# as14120_fpga_ddr.net
KiCad netlist of a schematic drawn in Altium Designer
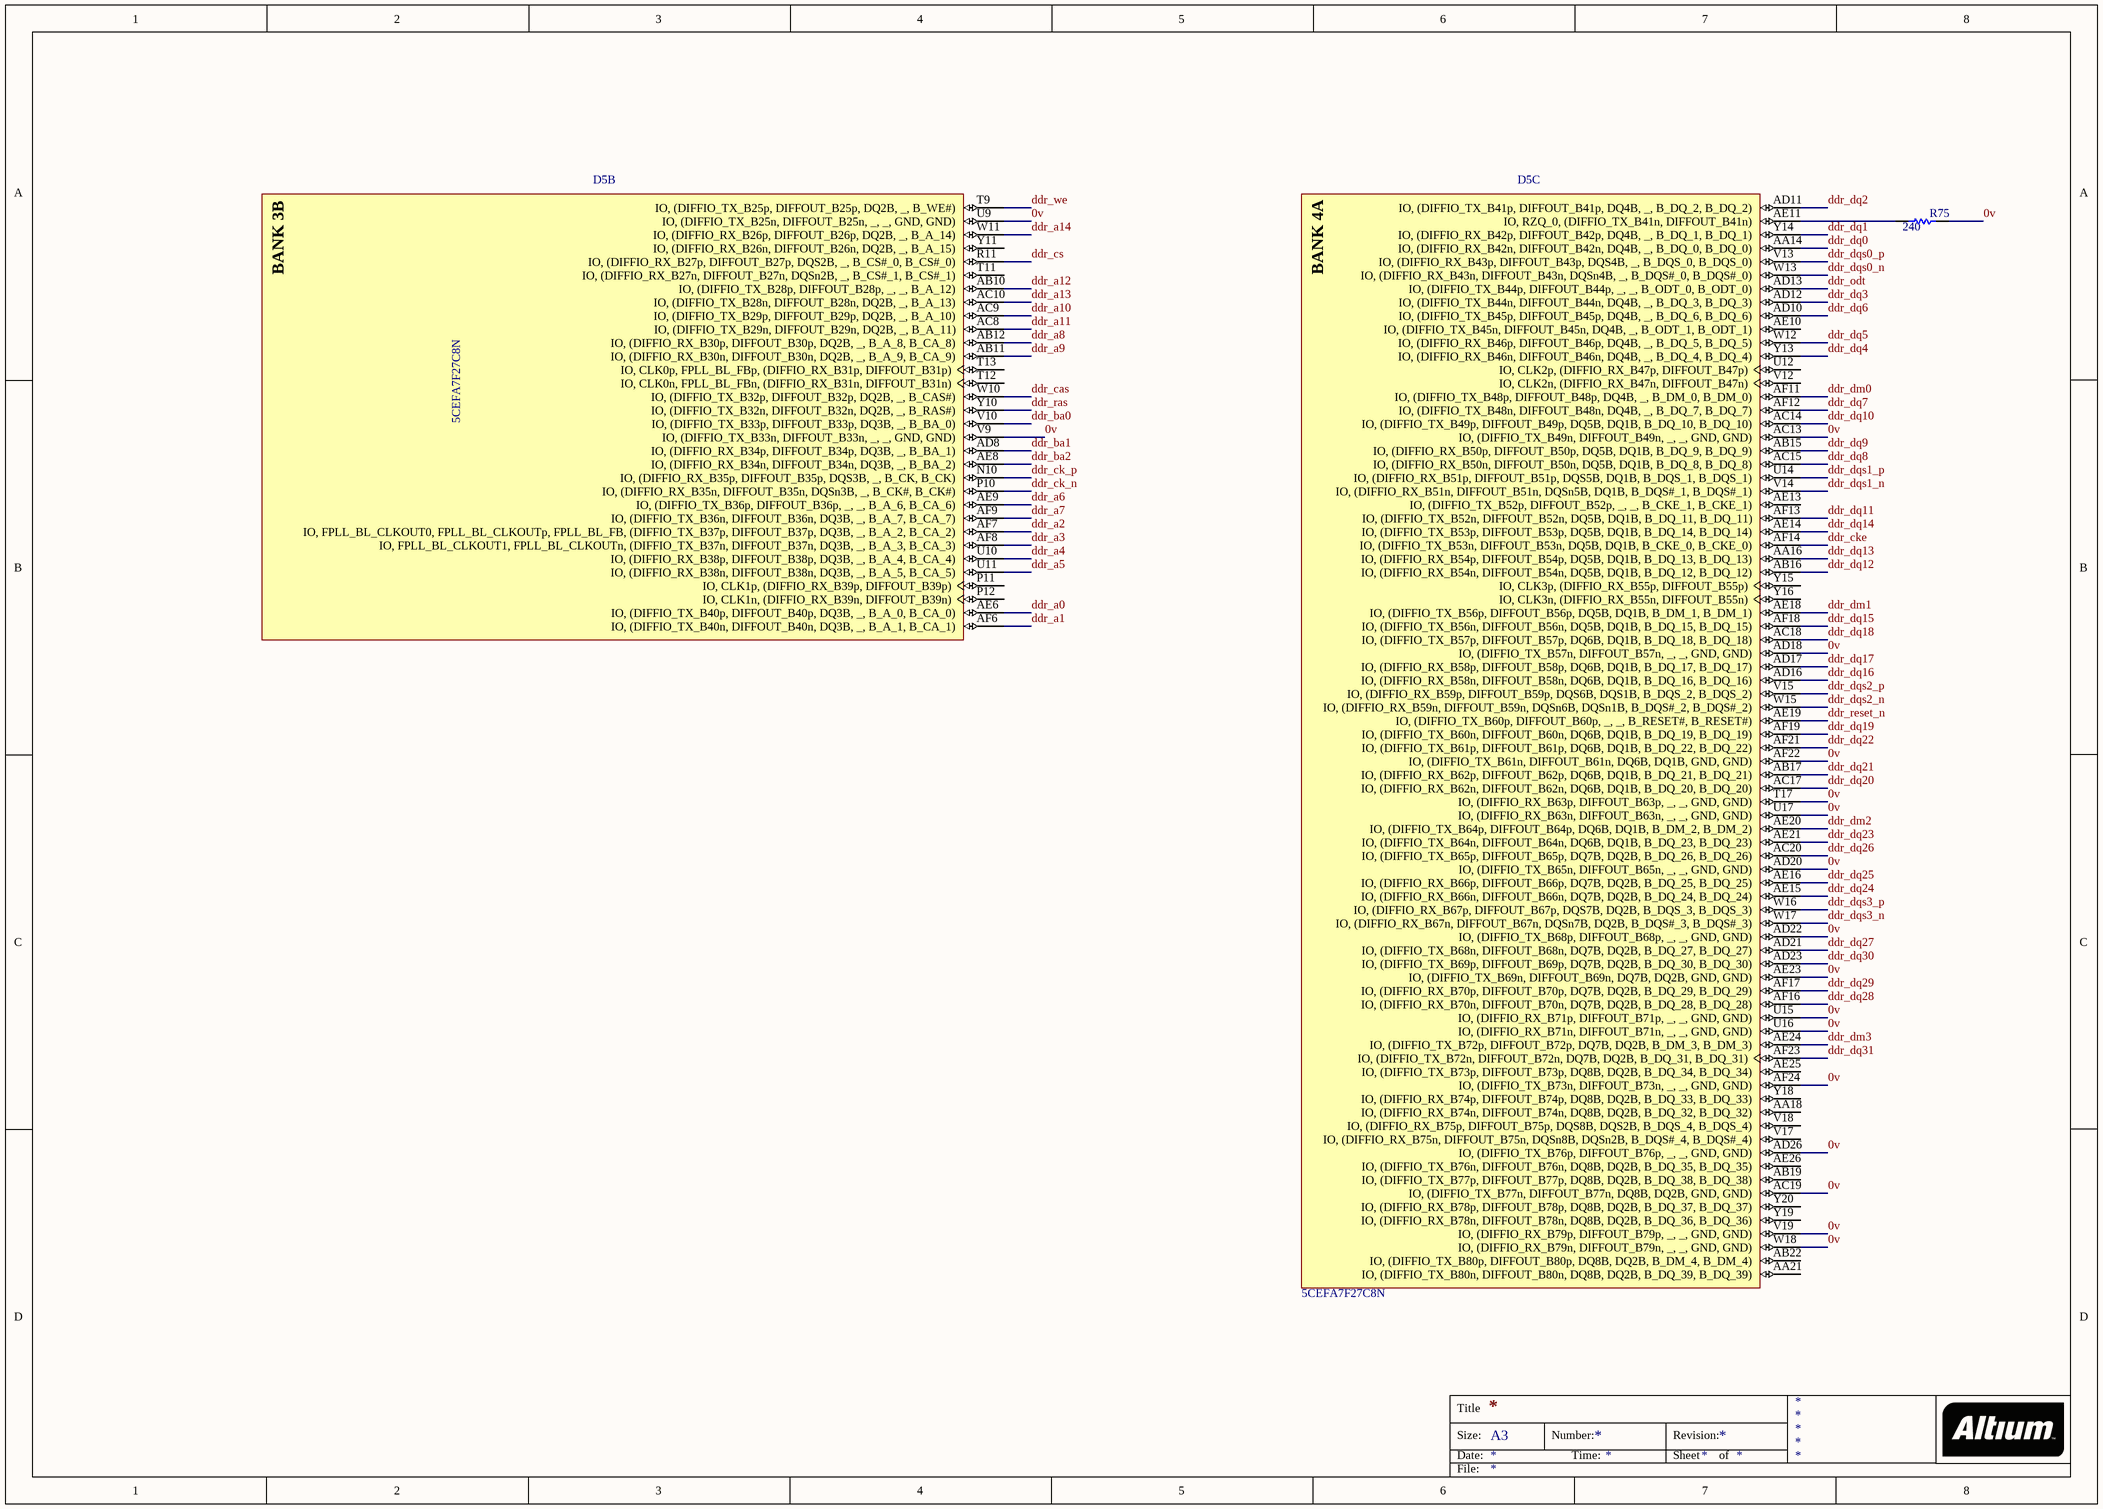
[diagram p0: as14120_fpga_ddr.SchDoc]

(export (version "E")
  (design (tool "Eeschema 10.0.6"))
  (components
    (comp (ref "D5")
      (value "5CEFA7F27C8N")
      (footprint "ALTR-672-FBGA-2000A")
      (fields (field (name "MANUFACTURER") "Altera"))
      (libsource (lib "Altera Cyclone V E") (part "5CEFA7F27C8N"))
    )
    (comp (ref "R75")
      (value "240")
      (footprint "RESC0805(2012)_L")
      (description "1K 0.125W 1% 0805 (2012 Metric)  SMD")
      (fields (field (name "TOLERANCE") "1 %") (field (name "POWER") "0.125 W"))
      (libsource (lib "as14120") (part "RES_0805"))
    )
  )
  (nets
    (net (code "1") (name "/0v") (class "Default")
      (node (ref "D5") (pin "AC13") (pinfunction "IO,_(DIFFIO_TX_B49n,_DIFFOUT_B49n,__,__,_GND,_GND)_AC13") (pintype "bidirectional"))
      (node (ref "D5") (pin "AC19") (pinfunction "IO,_(DIFFIO_TX_B77n,_DIFFOUT_B77n,_DQ8B,_DQ2B,_GND,_GND)_AC19") (pintype "bidirectional"))
      (node (ref "D5") (pin "AD18") (pinfunction "IO,_(DIFFIO_TX_B57n,_DIFFOUT_B57n,__,__,_GND,_GND)_AD18") (pintype "bidirectional"))
      (node (ref "D5") (pin "AD20") (pinfunction "IO,_(DIFFIO_TX_B65n,_DIFFOUT_B65n,__,__,_GND,_GND)_AD20") (pintype "bidirectional"))
      (node (ref "D5") (pin "AD22") (pinfunction "IO,_(DIFFIO_TX_B68p,_DIFFOUT_B68p,__,__,_GND,_GND)_AD22") (pintype "bidirectional"))
      (node (ref "D5") (pin "AD26") (pinfunction "IO,_(DIFFIO_TX_B76p,_DIFFOUT_B76p,__,__,_GND,_GND)_AD26") (pintype "bidirectional"))
      (node (ref "D5") (pin "AE23") (pinfunction "IO,_(DIFFIO_TX_B69n,_DIFFOUT_B69n,_DQ7B,_DQ2B,_GND,_GND)_AE23") (pintype "bidirectional"))
      (node (ref "D5") (pin "AF22") (pinfunction "IO,_(DIFFIO_TX_B61n,_DIFFOUT_B61n,_DQ6B,_DQ1B,_GND,_GND)_AF22") (pintype "bidirectional"))
      (node (ref "D5") (pin "AF24") (pinfunction "IO,_(DIFFIO_TX_B73n,_DIFFOUT_B73n,__,__,_GND,_GND)_AF24") (pintype "bidirectional"))
      (node (ref "D5") (pin "T17") (pinfunction "IO,_(DIFFIO_RX_B63p,_DIFFOUT_B63p,__,__,_GND,_GND)_T17") (pintype "bidirectional"))
      (node (ref "D5") (pin "U15") (pinfunction "IO,_(DIFFIO_RX_B71p,_DIFFOUT_B71p,__,__,_GND,_GND)_U15") (pintype "bidirectional"))
      (node (ref "D5") (pin "U16") (pinfunction "IO,_(DIFFIO_RX_B71n,_DIFFOUT_B71n,__,__,_GND,_GND)_U16") (pintype "bidirectional"))
      (node (ref "D5") (pin "U17") (pinfunction "IO,_(DIFFIO_RX_B63n,_DIFFOUT_B63n,__,__,_GND,_GND)_U17") (pintype "bidirectional"))
      (node (ref "D5") (pin "U9") (pinfunction "IO,_(DIFFIO_TX_B25n,_DIFFOUT_B25n,__,__,_GND,_GND)_U9") (pintype "bidirectional"))
      (node (ref "D5") (pin "V19") (pinfunction "IO,_(DIFFIO_RX_B79p,_DIFFOUT_B79p,__,__,_GND,_GND)_V19") (pintype "bidirectional"))
      (node (ref "D5") (pin "V9") (pinfunction "IO,_(DIFFIO_TX_B33n,_DIFFOUT_B33n,__,__,_GND,_GND)_V9") (pintype "bidirectional"))
      (node (ref "D5") (pin "W18") (pinfunction "IO,_(DIFFIO_RX_B79n,_DIFFOUT_B79n,__,__,_GND,_GND)_W18") (pintype "bidirectional"))
      (node (ref "R75") (pin "2") (pinfunction "2_2") (pintype "passive"))
    )
    (net (code "2") (name "/ddr_a0") (class "Default")
      (node (ref "D5") (pin "AE6") (pinfunction "IO,_(DIFFIO_TX_B40p,_DIFFOUT_B40p,_DQ3B,__,_B_A_0,_B_CA_0)_AE6") (pintype "bidirectional"))
    )
    (net (code "3") (name "/ddr_a1") (class "Default")
      (node (ref "D5") (pin "AF6") (pinfunction "IO,_(DIFFIO_TX_B40n,_DIFFOUT_B40n,_DQ3B,__,_B_A_1,_B_CA_1)_AF6") (pintype "bidirectional"))
    )
    (net (code "4") (name "/ddr_a2") (class "Default")
      (node (ref "D5") (pin "AF7") (pinfunction "IO,_FPLL_BL_CLKOUT0,_FPLL_BL_CLKOUTp,_FPLL_BL_FB,_(DIFFIO_TX_B37p,_DIFFOUT_B37p,_DQ3B,__,_B_A_2,_B_CA_2)_AF7") (pintype "bidirectional"))
    )
    (net (code "5") (name "/ddr_a3") (class "Default")
      (node (ref "D5") (pin "AF8") (pinfunction "IO,_FPLL_BL_CLKOUT1,_FPLL_BL_CLKOUTn,_(DIFFIO_TX_B37n,_DIFFOUT_B37n,_DQ3B,__,_B_A_3,_B_CA_3)_AF8") (pintype "bidirectional"))
    )
    (net (code "6") (name "/ddr_a4") (class "Default")
      (node (ref "D5") (pin "U10") (pinfunction "IO,_(DIFFIO_RX_B38p,_DIFFOUT_B38p,_DQ3B,__,_B_A_4,_B_CA_4)_U10") (pintype "bidirectional"))
    )
    (net (code "7") (name "/ddr_a5") (class "Default")
      (node (ref "D5") (pin "U11") (pinfunction "IO,_(DIFFIO_RX_B38n,_DIFFOUT_B38n,_DQ3B,__,_B_A_5,_B_CA_5)_U11") (pintype "bidirectional"))
    )
    (net (code "8") (name "/ddr_a6") (class "Default")
      (node (ref "D5") (pin "AE9") (pinfunction "IO,_(DIFFIO_TX_B36p,_DIFFOUT_B36p,__,__,_B_A_6,_B_CA_6)_AE9") (pintype "bidirectional"))
    )
    (net (code "9") (name "/ddr_a7") (class "Default")
      (node (ref "D5") (pin "AF9") (pinfunction "IO,_(DIFFIO_TX_B36n,_DIFFOUT_B36n,_DQ3B,__,_B_A_7,_B_CA_7)_AF9") (pintype "bidirectional"))
    )
    (net (code "10") (name "/ddr_a8") (class "Default")
      (node (ref "D5") (pin "AB12") (pinfunction "IO,_(DIFFIO_RX_B30p,_DIFFOUT_B30p,_DQ2B,__,_B_A_8,_B_CA_8)_AB12") (pintype "bidirectional"))
    )
    (net (code "11") (name "/ddr_a9") (class "Default")
      (node (ref "D5") (pin "AB11") (pinfunction "IO,_(DIFFIO_RX_B30n,_DIFFOUT_B30n,_DQ2B,__,_B_A_9,_B_CA_9)_AB11") (pintype "bidirectional"))
    )
    (net (code "12") (name "/ddr_a10") (class "Default")
      (node (ref "D5") (pin "AC9") (pinfunction "IO,_(DIFFIO_TX_B29p,_DIFFOUT_B29p,_DQ2B,__,_B_A_10)_AC9") (pintype "bidirectional"))
    )
    (net (code "13") (name "/ddr_a11") (class "Default")
      (node (ref "D5") (pin "AC8") (pinfunction "IO,_(DIFFIO_TX_B29n,_DIFFOUT_B29n,_DQ2B,__,_B_A_11)_AC8") (pintype "bidirectional"))
    )
    (net (code "14") (name "/ddr_a12") (class "Default")
      (node (ref "D5") (pin "AB10") (pinfunction "IO,_(DIFFIO_TX_B28p,_DIFFOUT_B28p,__,__,_B_A_12)_AB10") (pintype "bidirectional"))
    )
    (net (code "15") (name "/ddr_a13") (class "Default")
      (node (ref "D5") (pin "AC10") (pinfunction "IO,_(DIFFIO_TX_B28n,_DIFFOUT_B28n,_DQ2B,__,_B_A_13)_AC10") (pintype "bidirectional"))
    )
    (net (code "16") (name "/ddr_a14") (class "Default")
      (node (ref "D5") (pin "W11") (pinfunction "IO,_(DIFFIO_RX_B26p,_DIFFOUT_B26p,_DQ2B,__,_B_A_14)_W11") (pintype "bidirectional"))
    )
    (net (code "17") (name "/ddr_ba0") (class "Default")
      (node (ref "D5") (pin "V10") (pinfunction "IO,_(DIFFIO_TX_B33p,_DIFFOUT_B33p,_DQ3B,__,_B_BA_0)_V10") (pintype "bidirectional"))
    )
    (net (code "18") (name "/ddr_ba1") (class "Default")
      (node (ref "D5") (pin "AD8") (pinfunction "IO,_(DIFFIO_RX_B34p,_DIFFOUT_B34p,_DQ3B,__,_B_BA_1)_AD8") (pintype "bidirectional"))
    )
    (net (code "19") (name "/ddr_ba2") (class "Default")
      (node (ref "D5") (pin "AE8") (pinfunction "IO,_(DIFFIO_RX_B34n,_DIFFOUT_B34n,_DQ3B,__,_B_BA_2)_AE8") (pintype "bidirectional"))
    )
    (net (code "20") (name "/ddr_cas") (class "Default")
      (node (ref "D5") (pin "W10") (pinfunction "IO,_(DIFFIO_TX_B32p,_DIFFOUT_B32p,_DQ2B,__,_B_CAS#)_W10") (pintype "bidirectional"))
    )
    (net (code "21") (name "/ddr_ck_n") (class "Default")
      (node (ref "D5") (pin "P10") (pinfunction "IO,_(DIFFIO_RX_B35n,_DIFFOUT_B35n,_DQSn3B,__,_B_CK#,_B_CK#)_P10") (pintype "bidirectional"))
    )
    (net (code "22") (name "/ddr_ck_p") (class "Default")
      (node (ref "D5") (pin "N10") (pinfunction "IO,_(DIFFIO_RX_B35p,_DIFFOUT_B35p,_DQS3B,__,_B_CK,_B_CK)_N10") (pintype "bidirectional"))
    )
    (net (code "23") (name "/ddr_cke") (class "Default")
      (node (ref "D5") (pin "AF14") (pinfunction "IO,_(DIFFIO_TX_B53n,_DIFFOUT_B53n,_DQ5B,_DQ1B,_B_CKE_0,_B_CKE_0)_AF14") (pintype "bidirectional"))
    )
    (net (code "24") (name "/ddr_cs") (class "Default")
      (node (ref "D5") (pin "R11") (pinfunction "IO,_(DIFFIO_RX_B27p,_DIFFOUT_B27p,_DQS2B,__,_B_CS#_0,_B_CS#_0)_R11") (pintype "bidirectional"))
    )
    (net (code "25") (name "/ddr_dm0") (class "Default")
      (node (ref "D5") (pin "AF11") (pinfunction "IO,_(DIFFIO_TX_B48p,_DIFFOUT_B48p,_DQ4B,__,_B_DM_0,_B_DM_0)_AF11") (pintype "bidirectional"))
    )
    (net (code "26") (name "/ddr_dm1") (class "Default")
      (node (ref "D5") (pin "AE18") (pinfunction "IO,_(DIFFIO_TX_B56p,_DIFFOUT_B56p,_DQ5B,_DQ1B,_B_DM_1,_B_DM_1)_AE18") (pintype "bidirectional"))
    )
    (net (code "27") (name "/ddr_dm2") (class "Default")
      (node (ref "D5") (pin "AE20") (pinfunction "IO,_(DIFFIO_TX_B64p,_DIFFOUT_B64p,_DQ6B,_DQ1B,_B_DM_2,_B_DM_2)_AE20") (pintype "bidirectional"))
    )
    (net (code "28") (name "/ddr_dm3") (class "Default")
      (node (ref "D5") (pin "AE24") (pinfunction "IO,_(DIFFIO_TX_B72p,_DIFFOUT_B72p,_DQ7B,_DQ2B,_B_DM_3,_B_DM_3)_AE24") (pintype "bidirectional"))
    )
    (net (code "29") (name "/ddr_dq0") (class "Default")
      (node (ref "D5") (pin "AA14") (pinfunction "IO,_(DIFFIO_RX_B42n,_DIFFOUT_B42n,_DQ4B,__,_B_DQ_0,_B_DQ_0)_AA14") (pintype "bidirectional"))
    )
    (net (code "30") (name "/ddr_dq1") (class "Default")
      (node (ref "D5") (pin "Y14") (pinfunction "IO,_(DIFFIO_RX_B42p,_DIFFOUT_B42p,_DQ4B,__,_B_DQ_1,_B_DQ_1)_Y14") (pintype "bidirectional"))
    )
    (net (code "31") (name "/ddr_dq2") (class "Default")
      (node (ref "D5") (pin "AD11") (pinfunction "IO,_(DIFFIO_TX_B41p,_DIFFOUT_B41p,_DQ4B,__,_B_DQ_2,_B_DQ_2)_AD11") (pintype "bidirectional"))
    )
    (net (code "32") (name "/ddr_dq3") (class "Default")
      (node (ref "D5") (pin "AD12") (pinfunction "IO,_(DIFFIO_TX_B44n,_DIFFOUT_B44n,_DQ4B,__,_B_DQ_3,_B_DQ_3)_AD12") (pintype "bidirectional"))
    )
    (net (code "33") (name "/ddr_dq4") (class "Default")
      (node (ref "D5") (pin "Y13") (pinfunction "IO,_(DIFFIO_RX_B46n,_DIFFOUT_B46n,_DQ4B,__,_B_DQ_4,_B_DQ_4)_Y13") (pintype "bidirectional"))
    )
    (net (code "34") (name "/ddr_dq5") (class "Default")
      (node (ref "D5") (pin "W12") (pinfunction "IO,_(DIFFIO_RX_B46p,_DIFFOUT_B46p,_DQ4B,__,_B_DQ_5,_B_DQ_5)_W12") (pintype "bidirectional"))
    )
    (net (code "35") (name "/ddr_dq6") (class "Default")
      (node (ref "D5") (pin "AD10") (pinfunction "IO,_(DIFFIO_TX_B45p,_DIFFOUT_B45p,_DQ4B,__,_B_DQ_6,_B_DQ_6)_AD10") (pintype "bidirectional"))
    )
    (net (code "36") (name "/ddr_dq7") (class "Default")
      (node (ref "D5") (pin "AF12") (pinfunction "IO,_(DIFFIO_TX_B48n,_DIFFOUT_B48n,_DQ4B,__,_B_DQ_7,_B_DQ_7)_AF12") (pintype "bidirectional"))
    )
    (net (code "37") (name "/ddr_dq8") (class "Default")
      (node (ref "D5") (pin "AC15") (pinfunction "IO,_(DIFFIO_RX_B50n,_DIFFOUT_B50n,_DQ5B,_DQ1B,_B_DQ_8,_B_DQ_8)_AC15") (pintype "bidirectional"))
    )
    (net (code "38") (name "/ddr_dq9") (class "Default")
      (node (ref "D5") (pin "AB15") (pinfunction "IO,_(DIFFIO_RX_B50p,_DIFFOUT_B50p,_DQ5B,_DQ1B,_B_DQ_9,_B_DQ_9)_AB15") (pintype "bidirectional"))
    )
    (net (code "39") (name "/ddr_dq10") (class "Default")
      (node (ref "D5") (pin "AC14") (pinfunction "IO,_(DIFFIO_TX_B49p,_DIFFOUT_B49p,_DQ5B,_DQ1B,_B_DQ_10,_B_DQ_10)_AC14") (pintype "bidirectional"))
    )
    (net (code "40") (name "/ddr_dq11") (class "Default")
      (node (ref "D5") (pin "AF13") (pinfunction "IO,_(DIFFIO_TX_B52n,_DIFFOUT_B52n,_DQ5B,_DQ1B,_B_DQ_11,_B_DQ_11)_AF13") (pintype "bidirectional"))
    )
    (net (code "41") (name "/ddr_dq12") (class "Default")
      (node (ref "D5") (pin "AB16") (pinfunction "IO,_(DIFFIO_RX_B54n,_DIFFOUT_B54n,_DQ5B,_DQ1B,_B_DQ_12,_B_DQ_12)_AB16") (pintype "bidirectional"))
    )
    (net (code "42") (name "/ddr_dq13") (class "Default")
      (node (ref "D5") (pin "AA16") (pinfunction "IO,_(DIFFIO_RX_B54p,_DIFFOUT_B54p,_DQ5B,_DQ1B,_B_DQ_13,_B_DQ_13)_AA16") (pintype "bidirectional"))
    )
    (net (code "43") (name "/ddr_dq14") (class "Default")
      (node (ref "D5") (pin "AE14") (pinfunction "IO,_(DIFFIO_TX_B53p,_DIFFOUT_B53p,_DQ5B,_DQ1B,_B_DQ_14,_B_DQ_14)_AE14") (pintype "bidirectional"))
    )
    (net (code "44") (name "/ddr_dq15") (class "Default")
      (node (ref "D5") (pin "AF18") (pinfunction "IO,_(DIFFIO_TX_B56n,_DIFFOUT_B56n,_DQ5B,_DQ1B,_B_DQ_15,_B_DQ_15)_AF18") (pintype "bidirectional"))
    )
    (net (code "45") (name "/ddr_dq16") (class "Default")
      (node (ref "D5") (pin "AD16") (pinfunction "IO,_(DIFFIO_RX_B58n,_DIFFOUT_B58n,_DQ6B,_DQ1B,_B_DQ_16,_B_DQ_16)_AD16") (pintype "bidirectional"))
    )
    (net (code "46") (name "/ddr_dq17") (class "Default")
      (node (ref "D5") (pin "AD17") (pinfunction "IO,_(DIFFIO_RX_B58p,_DIFFOUT_B58p,_DQ6B,_DQ1B,_B_DQ_17,_B_DQ_17)_AD17") (pintype "bidirectional"))
    )
    (net (code "47") (name "/ddr_dq18") (class "Default")
      (node (ref "D5") (pin "AC18") (pinfunction "IO,_(DIFFIO_TX_B57p,_DIFFOUT_B57p,_DQ6B,_DQ1B,_B_DQ_18,_B_DQ_18)_AC18") (pintype "bidirectional"))
    )
    (net (code "48") (name "/ddr_dq19") (class "Default")
      (node (ref "D5") (pin "AF19") (pinfunction "IO,_(DIFFIO_TX_B60n,_DIFFOUT_B60n,_DQ6B,_DQ1B,_B_DQ_19,_B_DQ_19)_AF19") (pintype "bidirectional"))
    )
    (net (code "49") (name "/ddr_dq20") (class "Default")
      (node (ref "D5") (pin "AC17") (pinfunction "IO,_(DIFFIO_RX_B62n,_DIFFOUT_B62n,_DQ6B,_DQ1B,_B_DQ_20,_B_DQ_20)_AC17") (pintype "bidirectional"))
    )
    (net (code "50") (name "/ddr_dq21") (class "Default")
      (node (ref "D5") (pin "AB17") (pinfunction "IO,_(DIFFIO_RX_B62p,_DIFFOUT_B62p,_DQ6B,_DQ1B,_B_DQ_21,_B_DQ_21)_AB17") (pintype "bidirectional"))
    )
    (net (code "51") (name "/ddr_dq22") (class "Default")
      (node (ref "D5") (pin "AF21") (pinfunction "IO,_(DIFFIO_TX_B61p,_DIFFOUT_B61p,_DQ6B,_DQ1B,_B_DQ_22,_B_DQ_22)_AF21") (pintype "bidirectional"))
    )
    (net (code "52") (name "/ddr_dq23") (class "Default")
      (node (ref "D5") (pin "AE21") (pinfunction "IO,_(DIFFIO_TX_B64n,_DIFFOUT_B64n,_DQ6B,_DQ1B,_B_DQ_23,_B_DQ_23)_AE21") (pintype "bidirectional"))
    )
    (net (code "53") (name "/ddr_dq24") (class "Default")
      (node (ref "D5") (pin "AE15") (pinfunction "IO,_(DIFFIO_RX_B66n,_DIFFOUT_B66n,_DQ7B,_DQ2B,_B_DQ_24,_B_DQ_24)_AE15") (pintype "bidirectional"))
    )
    (net (code "54") (name "/ddr_dq25") (class "Default")
      (node (ref "D5") (pin "AE16") (pinfunction "IO,_(DIFFIO_RX_B66p,_DIFFOUT_B66p,_DQ7B,_DQ2B,_B_DQ_25,_B_DQ_25)_AE16") (pintype "bidirectional"))
    )
    (net (code "55") (name "/ddr_dq26") (class "Default")
      (node (ref "D5") (pin "AC20") (pinfunction "IO,_(DIFFIO_TX_B65p,_DIFFOUT_B65p,_DQ7B,_DQ2B,_B_DQ_26,_B_DQ_26)_AC20") (pintype "bidirectional"))
    )
    (net (code "56") (name "/ddr_dq27") (class "Default")
      (node (ref "D5") (pin "AD21") (pinfunction "IO,_(DIFFIO_TX_B68n,_DIFFOUT_B68n,_DQ7B,_DQ2B,_B_DQ_27,_B_DQ_27)_AD21") (pintype "bidirectional"))
    )
    (net (code "57") (name "/ddr_dq28") (class "Default")
      (node (ref "D5") (pin "AF16") (pinfunction "IO,_(DIFFIO_RX_B70n,_DIFFOUT_B70n,_DQ7B,_DQ2B,_B_DQ_28,_B_DQ_28)_AF16") (pintype "bidirectional"))
    )
    (net (code "58") (name "/ddr_dq29") (class "Default")
      (node (ref "D5") (pin "AF17") (pinfunction "IO,_(DIFFIO_RX_B70p,_DIFFOUT_B70p,_DQ7B,_DQ2B,_B_DQ_29,_B_DQ_29)_AF17") (pintype "bidirectional"))
    )
    (net (code "59") (name "/ddr_dq30") (class "Default")
      (node (ref "D5") (pin "AD23") (pinfunction "IO,_(DIFFIO_TX_B69p,_DIFFOUT_B69p,_DQ7B,_DQ2B,_B_DQ_30,_B_DQ_30)_AD23") (pintype "bidirectional"))
    )
    (net (code "60") (name "/ddr_dq31") (class "Default")
      (node (ref "D5") (pin "AF23") (pinfunction "IO,_(DIFFIO_TX_B72n,_DIFFOUT_B72n,_DQ7B,_DQ2B,_B_DQ_31,_B_DQ_31)_AF23") (pintype "bidirectional"))
    )
    (net (code "61") (name "/ddr_dqs0_n") (class "Default")
      (node (ref "D5") (pin "W13") (pinfunction "IO,_(DIFFIO_RX_B43n,_DIFFOUT_B43n,_DQSn4B,__,_B_DQS#_0,_B_DQS#_0)_W13") (pintype "bidirectional"))
    )
    (net (code "62") (name "/ddr_dqs0_p") (class "Default")
      (node (ref "D5") (pin "V13") (pinfunction "IO,_(DIFFIO_RX_B43p,_DIFFOUT_B43p,_DQS4B,__,_B_DQS_0,_B_DQS_0)_V13") (pintype "bidirectional"))
    )
    (net (code "63") (name "/ddr_dqs1_n") (class "Default")
      (node (ref "D5") (pin "V14") (pinfunction "IO,_(DIFFIO_RX_B51n,_DIFFOUT_B51n,_DQSn5B,_DQ1B,_B_DQS#_1,_B_DQS#_1)_V14") (pintype "bidirectional"))
    )
    (net (code "64") (name "/ddr_dqs1_p") (class "Default")
      (node (ref "D5") (pin "U14") (pinfunction "IO,_(DIFFIO_RX_B51p,_DIFFOUT_B51p,_DQS5B,_DQ1B,_B_DQS_1,_B_DQS_1)_U14") (pintype "bidirectional"))
    )
    (net (code "65") (name "/ddr_dqs2_n") (class "Default")
      (node (ref "D5") (pin "W15") (pinfunction "IO,_(DIFFIO_RX_B59n,_DIFFOUT_B59n,_DQSn6B,_DQSn1B,_B_DQS#_2,_B_DQS#_2)_W15") (pintype "bidirectional"))
    )
    (net (code "66") (name "/ddr_dqs2_p") (class "Default")
      (node (ref "D5") (pin "V15") (pinfunction "IO,_(DIFFIO_RX_B59p,_DIFFOUT_B59p,_DQS6B,_DQS1B,_B_DQS_2,_B_DQS_2)_V15") (pintype "bidirectional"))
    )
    (net (code "67") (name "/ddr_dqs3_n") (class "Default")
      (node (ref "D5") (pin "W17") (pinfunction "IO,_(DIFFIO_RX_B67n,_DIFFOUT_B67n,_DQSn7B,_DQ2B,_B_DQS#_3,_B_DQS#_3)_W17") (pintype "bidirectional"))
    )
    (net (code "68") (name "/ddr_dqs3_p") (class "Default")
      (node (ref "D5") (pin "W16") (pinfunction "IO,_(DIFFIO_RX_B67p,_DIFFOUT_B67p,_DQS7B,_DQ2B,_B_DQS_3,_B_DQS_3)_W16") (pintype "bidirectional"))
    )
    (net (code "69") (name "/ddr_odt") (class "Default")
      (node (ref "D5") (pin "AD13") (pinfunction "IO,_(DIFFIO_TX_B44p,_DIFFOUT_B44p,__,__,_B_ODT_0,_B_ODT_0)_AD13") (pintype "bidirectional"))
    )
    (net (code "70") (name "/ddr_ras") (class "Default")
      (node (ref "D5") (pin "Y10") (pinfunction "IO,_(DIFFIO_TX_B32n,_DIFFOUT_B32n,_DQ2B,__,_B_RAS#)_Y10") (pintype "bidirectional"))
    )
    (net (code "71") (name "/ddr_reset_n") (class "Default")
      (node (ref "D5") (pin "AE19") (pinfunction "IO,_(DIFFIO_TX_B60p,_DIFFOUT_B60p,__,__,_B_RESET#,_B_RESET#)_AE19") (pintype "bidirectional"))
    )
    (net (code "72") (name "/ddr_we") (class "Default")
      (node (ref "D5") (pin "T9") (pinfunction "IO,_(DIFFIO_TX_B25p,_DIFFOUT_B25p,_DQ2B,__,_B_WE#)_T9") (pintype "bidirectional"))
    )
    (net (code "73") (name "Net-(D5C-IO,_RZQ_0,_(DIFFIO_TX_B41n,_DIFFOUT_B41n))") (class "Default")
      (node (ref "D5") (pin "AE11") (pinfunction "IO,_RZQ_0,_(DIFFIO_TX_B41n,_DIFFOUT_B41n)_AE11") (pintype "bidirectional"))
      (node (ref "R75") (pin "1") (pinfunction "1_1") (pintype "passive"))
    )
    (net (code "74") (name "unconnected-(D5B-IO,_(DIFFIO_RX_B26n,_DIFFOUT_B26n,_DQ2B,__,_B_A_15)-PadY11)") (class "Default")
      (node (ref "D5") (pin "Y11") (pinfunction "IO,_(DIFFIO_RX_B26n,_DIFFOUT_B26n,_DQ2B,__,_B_A_15)_Y11") (pintype "bidirectional"))
    )
    (net (code "75") (name "unconnected-(D5B-IO,_(DIFFIO_RX_B27n,_DIFFOUT_B27n,_DQSn2B,__,_B_CS#_1,_B_CS#_1)-PadT11)") (class "Default")
      (node (ref "D5") (pin "T11") (pinfunction "IO,_(DIFFIO_RX_B27n,_DIFFOUT_B27n,_DQSn2B,__,_B_CS#_1,_B_CS#_1)_T11") (pintype "bidirectional"))
    )
    (net (code "76") (name "unconnected-(D5B-IO,_CLK0n,_FPLL_BL_FBn,_(DIFFIO_RX_B31n,_DIFFOUT_B31n)-PadT12)") (class "Default")
      (node (ref "D5") (pin "T12") (pinfunction "IO,_CLK0n,_FPLL_BL_FBn,_(DIFFIO_RX_B31n,_DIFFOUT_B31n)_T12") (pintype "bidirectional"))
    )
    (net (code "77") (name "unconnected-(D5B-IO,_CLK0p,_FPLL_BL_FBp,_(DIFFIO_RX_B31p,_DIFFOUT_B31p)-PadT13)") (class "Default")
      (node (ref "D5") (pin "T13") (pinfunction "IO,_CLK0p,_FPLL_BL_FBp,_(DIFFIO_RX_B31p,_DIFFOUT_B31p)_T13") (pintype "bidirectional"))
    )
    (net (code "78") (name "unconnected-(D5B-IO,_CLK1n,_(DIFFIO_RX_B39n,_DIFFOUT_B39n)-PadP12)") (class "Default")
      (node (ref "D5") (pin "P12") (pinfunction "IO,_CLK1n,_(DIFFIO_RX_B39n,_DIFFOUT_B39n)_P12") (pintype "bidirectional"))
    )
    (net (code "79") (name "unconnected-(D5B-IO,_CLK1p,_(DIFFIO_RX_B39p,_DIFFOUT_B39p)-PadP11)") (class "Default")
      (node (ref "D5") (pin "P11") (pinfunction "IO,_CLK1p,_(DIFFIO_RX_B39p,_DIFFOUT_B39p)_P11") (pintype "bidirectional"))
    )
    (net (code "80") (name "unconnected-(D5C-IO,_(DIFFIO_RX_B74n,_DIFFOUT_B74n,_DQ8B,_DQ2B,_B_DQ_32,_B_DQ_32)-PadAA18)") (class "Default")
      (node (ref "D5") (pin "AA18") (pinfunction "IO,_(DIFFIO_RX_B74n,_DIFFOUT_B74n,_DQ8B,_DQ2B,_B_DQ_32,_B_DQ_32)_AA18") (pintype "bidirectional"))
    )
    (net (code "81") (name "unconnected-(D5C-IO,_(DIFFIO_RX_B74p,_DIFFOUT_B74p,_DQ8B,_DQ2B,_B_DQ_33,_B_DQ_33)-PadY18)") (class "Default")
      (node (ref "D5") (pin "Y18") (pinfunction "IO,_(DIFFIO_RX_B74p,_DIFFOUT_B74p,_DQ8B,_DQ2B,_B_DQ_33,_B_DQ_33)_Y18") (pintype "bidirectional"))
    )
    (net (code "82") (name "unconnected-(D5C-IO,_(DIFFIO_RX_B75n,_DIFFOUT_B75n,_DQSn8B,_DQSn2B,_B_DQS#_4,_B_DQS#_4)-PadV17)") (class "Default")
      (node (ref "D5") (pin "V17") (pinfunction "IO,_(DIFFIO_RX_B75n,_DIFFOUT_B75n,_DQSn8B,_DQSn2B,_B_DQS#_4,_B_DQS#_4)_V17") (pintype "bidirectional"))
    )
    (net (code "83") (name "unconnected-(D5C-IO,_(DIFFIO_RX_B75p,_DIFFOUT_B75p,_DQS8B,_DQS2B,_B_DQS_4,_B_DQS_4)-PadV18)") (class "Default")
      (node (ref "D5") (pin "V18") (pinfunction "IO,_(DIFFIO_RX_B75p,_DIFFOUT_B75p,_DQS8B,_DQS2B,_B_DQS_4,_B_DQS_4)_V18") (pintype "bidirectional"))
    )
    (net (code "84") (name "unconnected-(D5C-IO,_(DIFFIO_RX_B78n,_DIFFOUT_B78n,_DQ8B,_DQ2B,_B_DQ_36,_B_DQ_36)-PadY19)") (class "Default")
      (node (ref "D5") (pin "Y19") (pinfunction "IO,_(DIFFIO_RX_B78n,_DIFFOUT_B78n,_DQ8B,_DQ2B,_B_DQ_36,_B_DQ_36)_Y19") (pintype "bidirectional"))
    )
    (net (code "85") (name "unconnected-(D5C-IO,_(DIFFIO_RX_B78p,_DIFFOUT_B78p,_DQ8B,_DQ2B,_B_DQ_37,_B_DQ_37)-PadY20)") (class "Default")
      (node (ref "D5") (pin "Y20") (pinfunction "IO,_(DIFFIO_RX_B78p,_DIFFOUT_B78p,_DQ8B,_DQ2B,_B_DQ_37,_B_DQ_37)_Y20") (pintype "bidirectional"))
    )
    (net (code "86") (name "unconnected-(D5C-IO,_(DIFFIO_TX_B45n,_DIFFOUT_B45n,_DQ4B,__,_B_ODT_1,_B_ODT_1)-PadAE10)") (class "Default")
      (node (ref "D5") (pin "AE10") (pinfunction "IO,_(DIFFIO_TX_B45n,_DIFFOUT_B45n,_DQ4B,__,_B_ODT_1,_B_ODT_1)_AE10") (pintype "bidirectional"))
    )
    (net (code "87") (name "unconnected-(D5C-IO,_(DIFFIO_TX_B52p,_DIFFOUT_B52p,__,__,_B_CKE_1,_B_CKE_1)-PadAE13)") (class "Default")
      (node (ref "D5") (pin "AE13") (pinfunction "IO,_(DIFFIO_TX_B52p,_DIFFOUT_B52p,__,__,_B_CKE_1,_B_CKE_1)_AE13") (pintype "bidirectional"))
    )
    (net (code "88") (name "unconnected-(D5C-IO,_(DIFFIO_TX_B73p,_DIFFOUT_B73p,_DQ8B,_DQ2B,_B_DQ_34,_B_DQ_34)-PadAE25)") (class "Default")
      (node (ref "D5") (pin "AE25") (pinfunction "IO,_(DIFFIO_TX_B73p,_DIFFOUT_B73p,_DQ8B,_DQ2B,_B_DQ_34,_B_DQ_34)_AE25") (pintype "bidirectional"))
    )
    (net (code "89") (name "unconnected-(D5C-IO,_(DIFFIO_TX_B76n,_DIFFOUT_B76n,_DQ8B,_DQ2B,_B_DQ_35,_B_DQ_35)-PadAE26)") (class "Default")
      (node (ref "D5") (pin "AE26") (pinfunction "IO,_(DIFFIO_TX_B76n,_DIFFOUT_B76n,_DQ8B,_DQ2B,_B_DQ_35,_B_DQ_35)_AE26") (pintype "bidirectional"))
    )
    (net (code "90") (name "unconnected-(D5C-IO,_(DIFFIO_TX_B77p,_DIFFOUT_B77p,_DQ8B,_DQ2B,_B_DQ_38,_B_DQ_38)-PadAB19)") (class "Default")
      (node (ref "D5") (pin "AB19") (pinfunction "IO,_(DIFFIO_TX_B77p,_DIFFOUT_B77p,_DQ8B,_DQ2B,_B_DQ_38,_B_DQ_38)_AB19") (pintype "bidirectional"))
    )
    (net (code "91") (name "unconnected-(D5C-IO,_(DIFFIO_TX_B80n,_DIFFOUT_B80n,_DQ8B,_DQ2B,_B_DQ_39,_B_DQ_39)-PadAA21)") (class "Default")
      (node (ref "D5") (pin "AA21") (pinfunction "IO,_(DIFFIO_TX_B80n,_DIFFOUT_B80n,_DQ8B,_DQ2B,_B_DQ_39,_B_DQ_39)_AA21") (pintype "bidirectional"))
    )
    (net (code "92") (name "unconnected-(D5C-IO,_(DIFFIO_TX_B80p,_DIFFOUT_B80p,_DQ8B,_DQ2B,_B_DM_4,_B_DM_4)-PadAB22)") (class "Default")
      (node (ref "D5") (pin "AB22") (pinfunction "IO,_(DIFFIO_TX_B80p,_DIFFOUT_B80p,_DQ8B,_DQ2B,_B_DM_4,_B_DM_4)_AB22") (pintype "bidirectional"))
    )
    (net (code "93") (name "unconnected-(D5C-IO,_CLK2n,_(DIFFIO_RX_B47n,_DIFFOUT_B47n)-PadV12)") (class "Default")
      (node (ref "D5") (pin "V12") (pinfunction "IO,_CLK2n,_(DIFFIO_RX_B47n,_DIFFOUT_B47n)_V12") (pintype "bidirectional"))
    )
    (net (code "94") (name "unconnected-(D5C-IO,_CLK2p,_(DIFFIO_RX_B47p,_DIFFOUT_B47p)-PadU12)") (class "Default")
      (node (ref "D5") (pin "U12") (pinfunction "IO,_CLK2p,_(DIFFIO_RX_B47p,_DIFFOUT_B47p)_U12") (pintype "bidirectional"))
    )
    (net (code "95") (name "unconnected-(D5C-IO,_CLK3n,_(DIFFIO_RX_B55n,_DIFFOUT_B55n)-PadY16)") (class "Default")
      (node (ref "D5") (pin "Y16") (pinfunction "IO,_CLK3n,_(DIFFIO_RX_B55n,_DIFFOUT_B55n)_Y16") (pintype "bidirectional"))
    )
    (net (code "96") (name "unconnected-(D5C-IO,_CLK3p,_(DIFFIO_RX_B55p,_DIFFOUT_B55p)-PadY15)") (class "Default")
      (node (ref "D5") (pin "Y15") (pinfunction "IO,_CLK3p,_(DIFFIO_RX_B55p,_DIFFOUT_B55p)_Y15") (pintype "bidirectional"))
    )
  )
)
